# RFM69_USB_Gateway_0_8.net
KiCad netlist of a schematic drawn in EAGLE
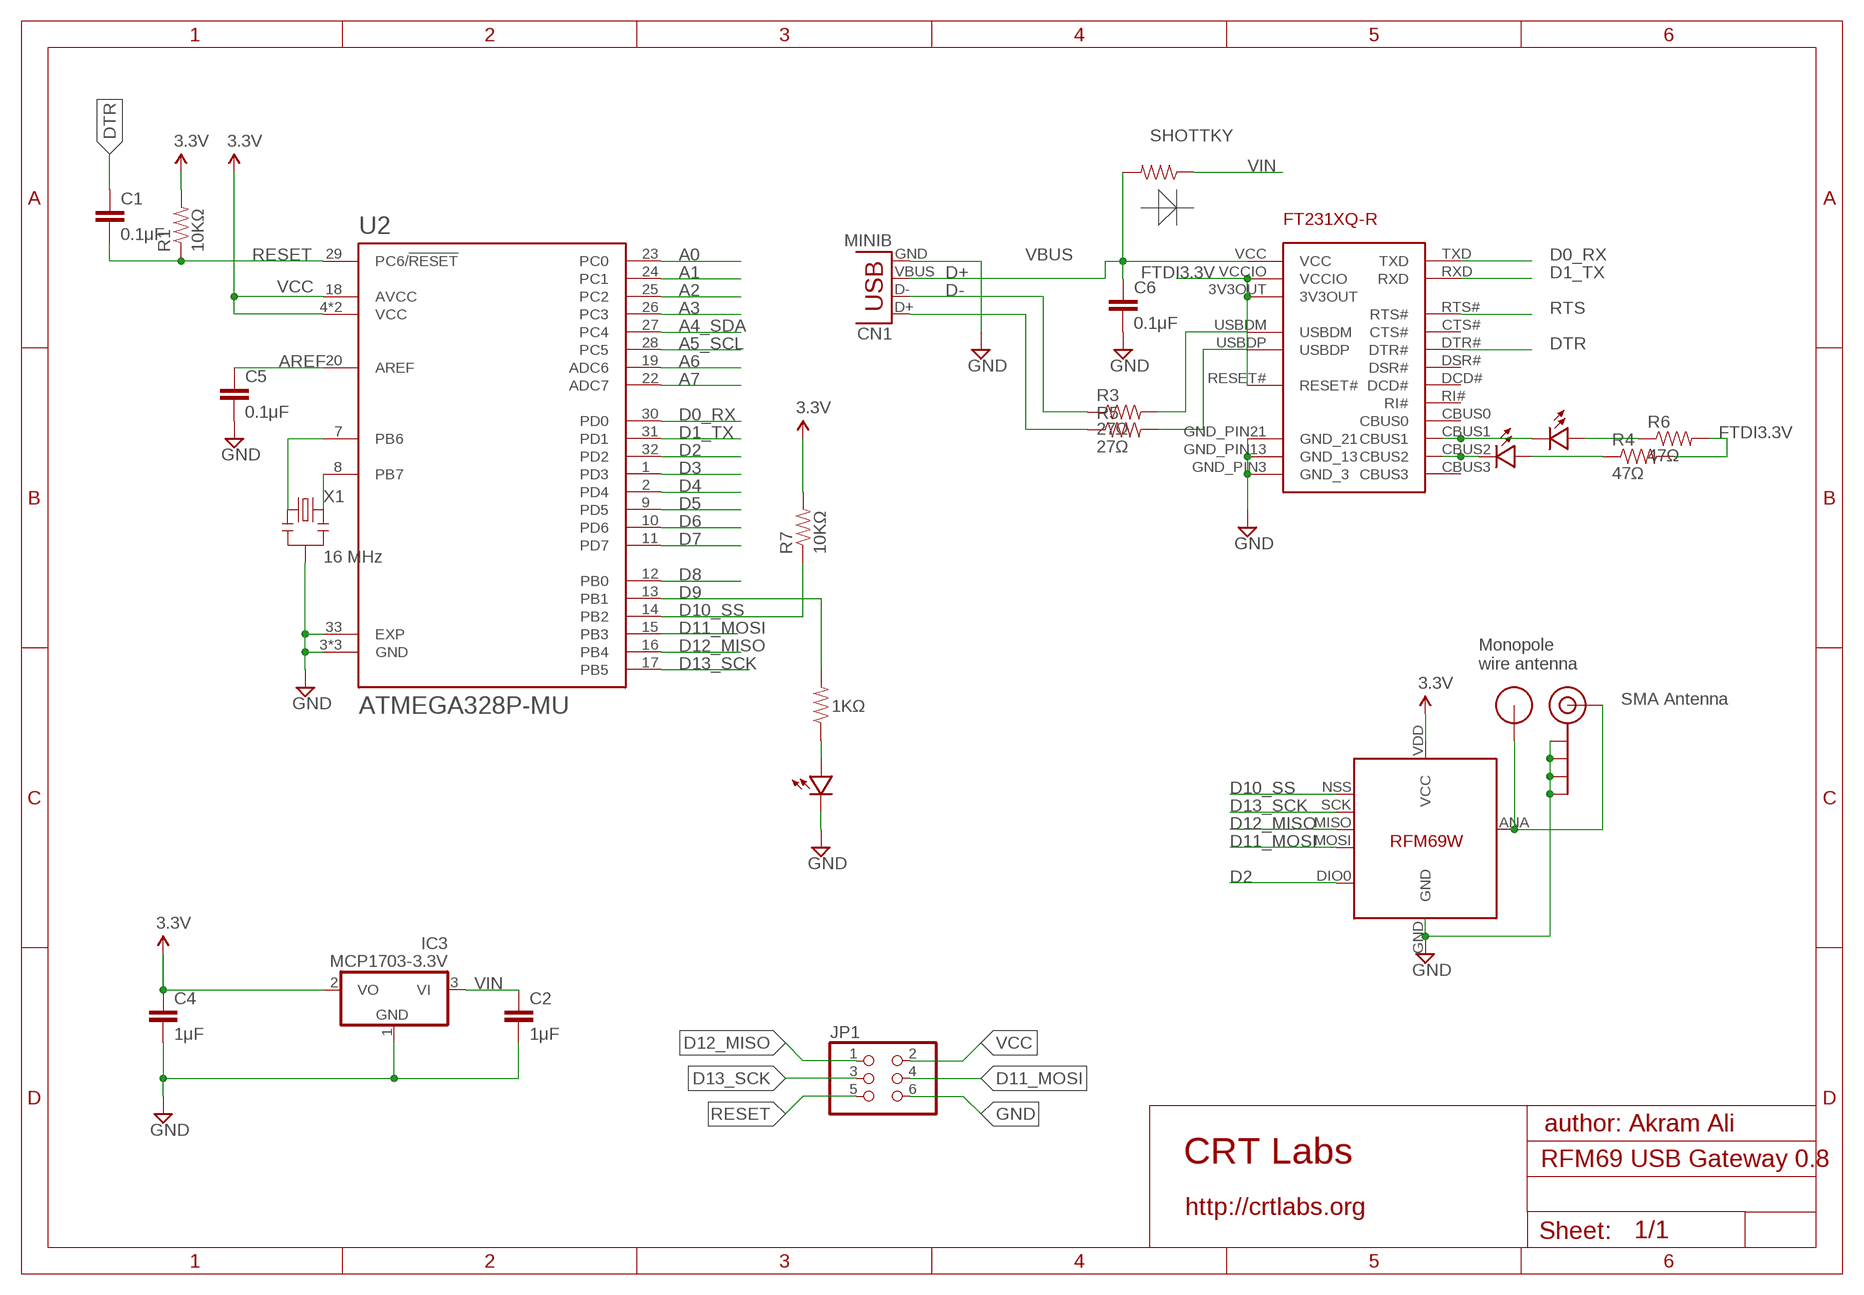
[diagram p0: schematic, sheet 1]

(export (version "E")
  (design (tool "Eeschema 10.0.6"))
  (components
    (comp (ref "C1")
      (value "0.1μF")
      (footprint "eagle-import:0805")
      (libsource (lib "eagle-import") (part "SparkFun_CAP0805"))
    )
    (comp (ref "C2")
      (value "1μF")
      (footprint "eagle-import:0805")
      (libsource (lib "eagle-import") (part "SparkFun_CAP0805"))
    )
    (comp (ref "C4")
      (value "1μF")
      (footprint "eagle-import:0805")
      (libsource (lib "eagle-import") (part "CAP0805"))
    )
    (comp (ref "C5")
      (value "0.1μF")
      (footprint "eagle-import:0805")
      (libsource (lib "eagle-import") (part "SparkFun_CAP0805"))
    )
    (comp (ref "C6")
      (value "0.1μF")
      (footprint "eagle-import:0805")
      (libsource (lib "eagle-import") (part "SparkFun_CAP0805"))
    )
    (comp (ref "CN1")
      (value "MINIB")
      (footprint "eagle-import:USB-A-H")
      (libsource (lib "eagle-import") (part "USB-A-H"))
    )
    (comp (ref "D")
      (value "SHOTTKY")
      (footprint "eagle-import:0805")
      (libsource (lib "eagle-import") (part "RESISTOR0805"))
    )
    (comp (ref "FT231XQ-R")
      (value "FT231XQ-R")
      (footprint "eagle-import:FTDI_FT231XQ-R_PACKAGE")
      (libsource (lib "eagle-import") (part "FT231XQ-R"))
    )
    (comp (ref "IC3")
      (value "MCP1703-3.3V")
      (footprint "eagle-import:SOT23")
      (libsource (lib "eagle-import") (part "MCP1703CB"))
    )
    (comp (ref "J$1")
      (value "SMA_EDGE")
      (footprint "eagle-import:SMA-EDGE")
      (libsource (lib "eagle-import") (part "SMA_EDGE"))
    )
    (comp (ref "JP1")
      (value "PINHD-2X3")
      (footprint "eagle-import:2X03")
      (libsource (lib "eagle-import") (part "PINHD-2X3"))
    )
    (comp (ref "R1")
      (value "10KΩ")
      (footprint "eagle-import:0805")
      (libsource (lib "eagle-import") (part "RESISTOR0805"))
    )
    (comp (ref "R2")
      (value "1KΩ")
      (footprint "eagle-import:0805")
      (libsource (lib "eagle-import") (part "SparkFun_RESISTOR0805-RES"))
    )
    (comp (ref "R3")
      (value "27Ω")
      (footprint "eagle-import:0805")
      (libsource (lib "eagle-import") (part "SparkFun_RESISTOR0805-RES"))
    )
    (comp (ref "R4")
      (value "47Ω")
      (footprint "eagle-import:0805")
      (libsource (lib "eagle-import") (part "SparkFun_RESISTOR0805-RES"))
    )
    (comp (ref "R5")
      (value "27Ω")
      (footprint "eagle-import:0805")
      (libsource (lib "eagle-import") (part "SparkFun_RESISTOR0805-RES"))
    )
    (comp (ref "R6")
      (value "47Ω")
      (footprint "eagle-import:0805")
      (libsource (lib "eagle-import") (part "SparkFun_RESISTOR0805-RES"))
    )
    (comp (ref "R7")
      (value "10KΩ")
      (footprint "eagle-import:0805")
      (libsource (lib "eagle-import") (part "SparkFun_RESISTOR0805-RES"))
    )
    (comp (ref "RX")
      (value "Green")
      (footprint "eagle-import:0805-LED")
      (libsource (lib "eagle-import") (part "LED0805"))
    )
    (comp (ref "TX")
      (value "Red")
      (footprint "eagle-import:0805-LED")
      (libsource (lib "eagle-import") (part "LED0805"))
    )
    (comp (ref "U$1")
      (value "RFM12B_ANTENNA")
      (footprint "eagle-import:RFM12B-ANTENNA")
      (libsource (lib "eagle-import") (part "RFM12B_ANTENNA"))
    )
    (comp (ref "U$2")
      (value "Status")
      (footprint "eagle-import:0805-LED")
      (libsource (lib "eagle-import") (part "LED0805"))
    )
    (comp (ref "U$5")
      (value "RFM69")
      (footprint "eagle-import:RFM69W-MINPADS")
      (libsource (lib "eagle-import") (part "RFM69"))
    )
    (comp (ref "U2")
      (value "ATMEGA328P-MU")
      (footprint "eagle-import:QFN50P500X500X100-33N")
      (fields (field (name "MF") "Atmel"))
      (libsource (lib "eagle-import") (part "ATMEGA328P-MU"))
    )
    (comp (ref "X1")
      (value "16 MHz")
      (footprint "eagle-import:RESONATOR-SMD")
      (libsource (lib "eagle-import") (part "RESONATORSMD"))
    )
  )
  (nets
    (net (code "1") (name "/A0") (class "Default")
      (node (ref "U2") (pin "23") (pinfunction "PC0_23") (pintype "bidirectional"))
    )
    (net (code "2") (name "/A1") (class "Default")
      (node (ref "U2") (pin "24") (pinfunction "PC1_24") (pintype "bidirectional"))
    )
    (net (code "3") (name "/A2") (class "Default")
      (node (ref "U2") (pin "25") (pinfunction "PC2_25") (pintype "bidirectional"))
    )
    (net (code "4") (name "/A3") (class "Default")
      (node (ref "U2") (pin "26") (pinfunction "PC3_26") (pintype "bidirectional"))
    )
    (net (code "5") (name "/A4_SDA") (class "Default")
      (node (ref "U2") (pin "27") (pinfunction "PC4_27") (pintype "bidirectional"))
    )
    (net (code "6") (name "/A5_SCL") (class "Default")
      (node (ref "U2") (pin "28") (pinfunction "PC5_28") (pintype "bidirectional"))
    )
    (net (code "7") (name "/A6") (class "Default")
      (node (ref "U2") (pin "19") (pinfunction "ADC6_19") (pintype "bidirectional"))
    )
    (net (code "8") (name "/A7") (class "Default")
      (node (ref "U2") (pin "22") (pinfunction "ADC7_22") (pintype "bidirectional"))
    )
    (net (code "9") (name "/AREF") (class "Default")
      (node (ref "C5") (pin "1") (pinfunction "1_1") (pintype "passive"))
      (node (ref "U2") (pin "20") (pinfunction "AREF_20") (pintype "input"))
    )
    (net (code "10") (name "/D+") (class "Default")
      (node (ref "CN1") (pin "D+") (pinfunction "D+_D+") (pintype "bidirectional"))
      (node (ref "R5") (pin "1") (pinfunction "1_1") (pintype "passive"))
    )
    (net (code "11") (name "/D-") (class "Default")
      (node (ref "CN1") (pin "D-") (pinfunction "D-_D-") (pintype "bidirectional"))
      (node (ref "R3") (pin "1") (pinfunction "1_1") (pintype "passive"))
    )
    (net (code "12") (name "/D0_RX") (class "Default")
      (node (ref "FT231XQ-R") (pin "TXD") (pinfunction "TXD_TXD") (pintype "bidirectional"))
      (node (ref "U2") (pin "30") (pinfunction "PD0_30") (pintype "bidirectional"))
    )
    (net (code "13") (name "/D1_TX") (class "Default")
      (node (ref "FT231XQ-R") (pin "RXD") (pinfunction "RXD_RXD") (pintype "bidirectional"))
      (node (ref "U2") (pin "31") (pinfunction "PD1_31") (pintype "bidirectional"))
    )
    (net (code "14") (name "/D2") (class "Default")
      (node (ref "U$5") (pin "DIO0") (pinfunction "DIO0_DIO0") (pintype "open_collector"))
      (node (ref "U2") (pin "32") (pinfunction "PD2_32") (pintype "bidirectional"))
    )
    (net (code "15") (name "/D3") (class "Default")
      (node (ref "U2") (pin "1") (pinfunction "PD3_1") (pintype "bidirectional"))
    )
    (net (code "16") (name "/D4") (class "Default")
      (node (ref "U2") (pin "2") (pinfunction "PD4_2") (pintype "bidirectional"))
    )
    (net (code "17") (name "/D5") (class "Default")
      (node (ref "U2") (pin "9") (pinfunction "PD5_9") (pintype "bidirectional"))
    )
    (net (code "18") (name "/D6") (class "Default")
      (node (ref "U2") (pin "10") (pinfunction "PD6_10") (pintype "bidirectional"))
    )
    (net (code "19") (name "/D7") (class "Default")
      (node (ref "U2") (pin "11") (pinfunction "PD7_11") (pintype "bidirectional"))
    )
    (net (code "20") (name "/D8") (class "Default")
      (node (ref "U2") (pin "12") (pinfunction "PB0_12") (pintype "bidirectional"))
    )
    (net (code "21") (name "/D9") (class "Default")
      (node (ref "R2") (pin "2") (pinfunction "2_2") (pintype "passive"))
      (node (ref "U2") (pin "13") (pinfunction "PB1_13") (pintype "bidirectional"))
    )
    (net (code "22") (name "/D10_SS") (class "Default")
      (node (ref "R7") (pin "1") (pinfunction "1_1") (pintype "passive"))
      (node (ref "U$5") (pin "NSS") (pinfunction "SEL_NSS") (pintype "input"))
      (node (ref "U2") (pin "14") (pinfunction "PB2_14") (pintype "bidirectional"))
    )
    (net (code "23") (name "/FTDI3.3V") (class "Default")
      (node (ref "FT231XQ-R") (pin "3V3OUT") (pinfunction "3V3OUT_3V3OUT") (pintype "bidirectional"))
      (node (ref "FT231XQ-R") (pin "RESET#") (pinfunction "RESET#_RESET#") (pintype "bidirectional"))
      (node (ref "FT231XQ-R") (pin "VCCIO") (pinfunction "VCCIO_VCCIO") (pintype "bidirectional"))
      (node (ref "R4") (pin "2") (pinfunction "2_2") (pintype "passive"))
      (node (ref "R6") (pin "2") (pinfunction "2_2") (pintype "passive"))
    )
    (net (code "24") (name "/RTS") (class "Default")
      (node (ref "FT231XQ-R") (pin "RTS#") (pinfunction "RTS#_RTS#") (pintype "bidirectional"))
    )
    (net (code "25") (name "/VBUS") (class "Default")
      (node (ref "C6") (pin "1") (pinfunction "1_1") (pintype "passive"))
      (node (ref "CN1") (pin "VBUS") (pinfunction "VBUS_VBUS") (pintype "bidirectional"))
      (node (ref "D") (pin "2") (pinfunction "2_2") (pintype "passive"))
      (node (ref "FT231XQ-R") (pin "VCC") (pinfunction "VCC_VCC") (pintype "bidirectional"))
    )
    (net (code "26") (name "/VIN") (class "Default")
      (node (ref "C2") (pin "1") (pinfunction "1_1") (pintype "passive"))
      (node (ref "D") (pin "1") (pinfunction "1_1") (pintype "passive"))
      (node (ref "IC3") (pin "3") (pinfunction "VI_3") (pintype "input"))
    )
    (net (code "27") (name "D11_MOSI") (class "Default")
      (node (ref "JP1") (pin "4") (pinfunction "4_4") (pintype "passive"))
      (node (ref "U$5") (pin "MOSI") (pinfunction "MOSI_MOSI") (pintype "output"))
      (node (ref "U2") (pin "15") (pinfunction "PB3_15") (pintype "bidirectional"))
    )
    (net (code "28") (name "D12_MISO") (class "Default")
      (node (ref "JP1") (pin "1") (pinfunction "1_1") (pintype "passive"))
      (node (ref "U$5") (pin "MISO") (pinfunction "MISO_MISO") (pintype "input"))
      (node (ref "U2") (pin "16") (pinfunction "PB4_16") (pintype "bidirectional"))
    )
    (net (code "29") (name "D13_SCK") (class "Default")
      (node (ref "JP1") (pin "3") (pinfunction "3_3") (pintype "passive"))
      (node (ref "U$5") (pin "SCK") (pinfunction "SCK_SCK") (pintype "input"))
      (node (ref "U2") (pin "17") (pinfunction "PB5_17") (pintype "bidirectional"))
    )
    (net (code "30") (name "DTR") (class "Default")
      (node (ref "C1") (pin "1") (pinfunction "1_1") (pintype "passive"))
      (node (ref "FT231XQ-R") (pin "DTR#") (pinfunction "DTR#_DTR#") (pintype "bidirectional"))
    )
    (net (code "31") (name "GND") (class "Default")
      (node (ref "C2") (pin "2") (pinfunction "2_2") (pintype "passive"))
      (node (ref "C4") (pin "2") (pinfunction "2_2") (pintype "passive"))
      (node (ref "C5") (pin "2") (pinfunction "2_2") (pintype "passive"))
      (node (ref "C6") (pin "2") (pinfunction "2_2") (pintype "passive"))
      (node (ref "CN1") (pin "GND") (pinfunction "GND_GND") (pintype "bidirectional"))
      (node (ref "FT231XQ-R") (pin "GND_PIN13") (pinfunction "GND_13_GND_PIN13") (pintype "bidirectional"))
      (node (ref "FT231XQ-R") (pin "GND_PIN21") (pinfunction "GND_21_GND_PIN21") (pintype "bidirectional"))
      (node (ref "FT231XQ-R") (pin "GND_PIN3") (pinfunction "GND_3_GND_PIN3") (pintype "bidirectional"))
      (node (ref "IC3") (pin "1") (pinfunction "GND_1") (pintype "passive"))
      (node (ref "J$1") (pin "GND@0") (pinfunction "GND_GND@0") (pintype "bidirectional"))
      (node (ref "J$1") (pin "GND@1") (pinfunction "GND_GND@1") (pintype "bidirectional"))
      (node (ref "J$1") (pin "GND@2") (pinfunction "GND_GND@2") (pintype "bidirectional"))
      (node (ref "J$1") (pin "GND@3") (pinfunction "GND_GND@3") (pintype "bidirectional"))
      (node (ref "JP1") (pin "6") (pinfunction "6_6") (pintype "passive"))
      (node (ref "U$2") (pin "MINUS") (pinfunction "MINUS_MINUS") (pintype "passive"))
      (node (ref "U$5") (pin "GND") (pinfunction "GND_GND") (pintype "power_in"))
      (node (ref "U2") (pin "21") (pinfunction "GND_21") (pintype "power_in"))
      (node (ref "U2") (pin "3") (pinfunction "GND_3") (pintype "power_in"))
      (node (ref "U2") (pin "33") (pinfunction "EXP_33") (pintype "power_in"))
      (node (ref "U2") (pin "5") (pinfunction "GND_5") (pintype "power_in"))
      (node (ref "X1") (pin "2") (pinfunction "2_2") (pintype "passive"))
    )
    (net (code "32") (name "Net-(FT231XQ-R-PadCBUS1)") (class "Default")
      (node (ref "FT231XQ-R") (pin "CBUS1") (pinfunction "CBUS1_CBUS1") (pintype "bidirectional"))
      (node (ref "RX") (pin "MINUS") (pinfunction "MINUS_MINUS") (pintype "passive"))
    )
    (net (code "33") (name "Net-(FT231XQ-R-PadCBUS2)") (class "Default")
      (node (ref "FT231XQ-R") (pin "CBUS2") (pinfunction "CBUS2_CBUS2") (pintype "bidirectional"))
      (node (ref "TX") (pin "MINUS") (pinfunction "MINUS_MINUS") (pintype "passive"))
    )
    (net (code "34") (name "Net-(FT231XQ-R-PadUSBDM)") (class "Default")
      (node (ref "FT231XQ-R") (pin "USBDM") (pinfunction "USBDM_USBDM") (pintype "bidirectional"))
      (node (ref "R3") (pin "2") (pinfunction "2_2") (pintype "passive"))
    )
    (net (code "35") (name "Net-(FT231XQ-R-PadUSBDP)") (class "Default")
      (node (ref "FT231XQ-R") (pin "USBDP") (pinfunction "USBDP_USBDP") (pintype "bidirectional"))
      (node (ref "R5") (pin "2") (pinfunction "2_2") (pintype "passive"))
    )
    (net (code "36") (name "Net-(J$1-SIGNAL)") (class "Default")
      (node (ref "J$1") (pin "SIG") (pinfunction "SIGNAL_SIG") (pintype "bidirectional"))
      (node (ref "U$1") (pin "P$1") (pinfunction "1_P$1") (pintype "bidirectional"))
      (node (ref "U$5") (pin "ANA") (pinfunction "ANT_ANA") (pintype "passive"))
    )
    (net (code "37") (name "Net-(R2-Pad1)") (class "Default")
      (node (ref "R2") (pin "1") (pinfunction "1_1") (pintype "passive"))
      (node (ref "U$2") (pin "PLUS") (pinfunction "PLUS_PLUS") (pintype "passive"))
    )
    (net (code "38") (name "Net-(R4-Pad1)") (class "Default")
      (node (ref "R4") (pin "1") (pinfunction "1_1") (pintype "passive"))
      (node (ref "TX") (pin "PLUS") (pinfunction "PLUS_PLUS") (pintype "passive"))
    )
    (net (code "39") (name "Net-(R6-Pad1)") (class "Default")
      (node (ref "R6") (pin "1") (pinfunction "1_1") (pintype "passive"))
      (node (ref "RX") (pin "PLUS") (pinfunction "PLUS_PLUS") (pintype "passive"))
    )
    (net (code "40") (name "Net-(U2-PB6)") (class "Default")
      (node (ref "U2") (pin "7") (pinfunction "PB6_7") (pintype "bidirectional"))
      (node (ref "X1") (pin "1") (pinfunction "1_1") (pintype "passive"))
    )
    (net (code "41") (name "Net-(U2-PB7)") (class "Default")
      (node (ref "U2") (pin "8") (pinfunction "PB7_8") (pintype "bidirectional"))
      (node (ref "X1") (pin "3") (pinfunction "3_3") (pintype "passive"))
    )
    (net (code "42") (name "RESET") (class "Default")
      (node (ref "C1") (pin "2") (pinfunction "2_2") (pintype "passive"))
      (node (ref "JP1") (pin "5") (pinfunction "5_5") (pintype "passive"))
      (node (ref "R1") (pin "1") (pinfunction "1_1") (pintype "passive"))
      (node (ref "U2") (pin "29") (pinfunction "PC6/~{RESET}_29") (pintype "bidirectional"))
    )
    (net (code "43") (name "VCC") (class "Default")
      (node (ref "C4") (pin "1") (pinfunction "1_1") (pintype "passive"))
      (node (ref "IC3") (pin "2") (pinfunction "VO_2") (pintype "passive"))
      (node (ref "JP1") (pin "2") (pinfunction "2_2") (pintype "passive"))
      (node (ref "R1") (pin "2") (pinfunction "2_2") (pintype "passive"))
      (node (ref "R7") (pin "2") (pinfunction "2_2") (pintype "passive"))
      (node (ref "U$5") (pin "VDD") (pinfunction "VCC_VDD") (pintype "power_in"))
      (node (ref "U2") (pin "18") (pinfunction "AVCC_18") (pintype "power_in"))
      (node (ref "U2") (pin "4") (pinfunction "VCC_4") (pintype "power_in"))
      (node (ref "U2") (pin "6") (pinfunction "VCC_6") (pintype "power_in"))
    )
    (net (code "44") (name "unconnected-(FT231XQ-R-PadCBUS0)") (class "Default")
      (node (ref "FT231XQ-R") (pin "CBUS0") (pinfunction "CBUS0_CBUS0") (pintype "bidirectional"))
    )
    (net (code "45") (name "unconnected-(FT231XQ-R-PadCBUS3)") (class "Default")
      (node (ref "FT231XQ-R") (pin "CBUS3") (pinfunction "CBUS3_CBUS3") (pintype "bidirectional"))
    )
    (net (code "46") (name "unconnected-(FT231XQ-R-PadCTS#)") (class "Default")
      (node (ref "FT231XQ-R") (pin "CTS#") (pinfunction "CTS#_CTS#") (pintype "bidirectional"))
    )
    (net (code "47") (name "unconnected-(FT231XQ-R-PadDCD#)") (class "Default")
      (node (ref "FT231XQ-R") (pin "DCD#") (pinfunction "DCD#_DCD#") (pintype "bidirectional"))
    )
    (net (code "48") (name "unconnected-(FT231XQ-R-PadDSR#)") (class "Default")
      (node (ref "FT231XQ-R") (pin "DSR#") (pinfunction "DSR#_DSR#") (pintype "bidirectional"))
    )
    (net (code "49") (name "unconnected-(FT231XQ-R-PadRI#)") (class "Default")
      (node (ref "FT231XQ-R") (pin "RI#") (pinfunction "RI#_RI#") (pintype "bidirectional"))
    )
  )
)
